# esp-streamer-schematics.net
KiCad netlist of a schematic drawn in EasyEDA Pro
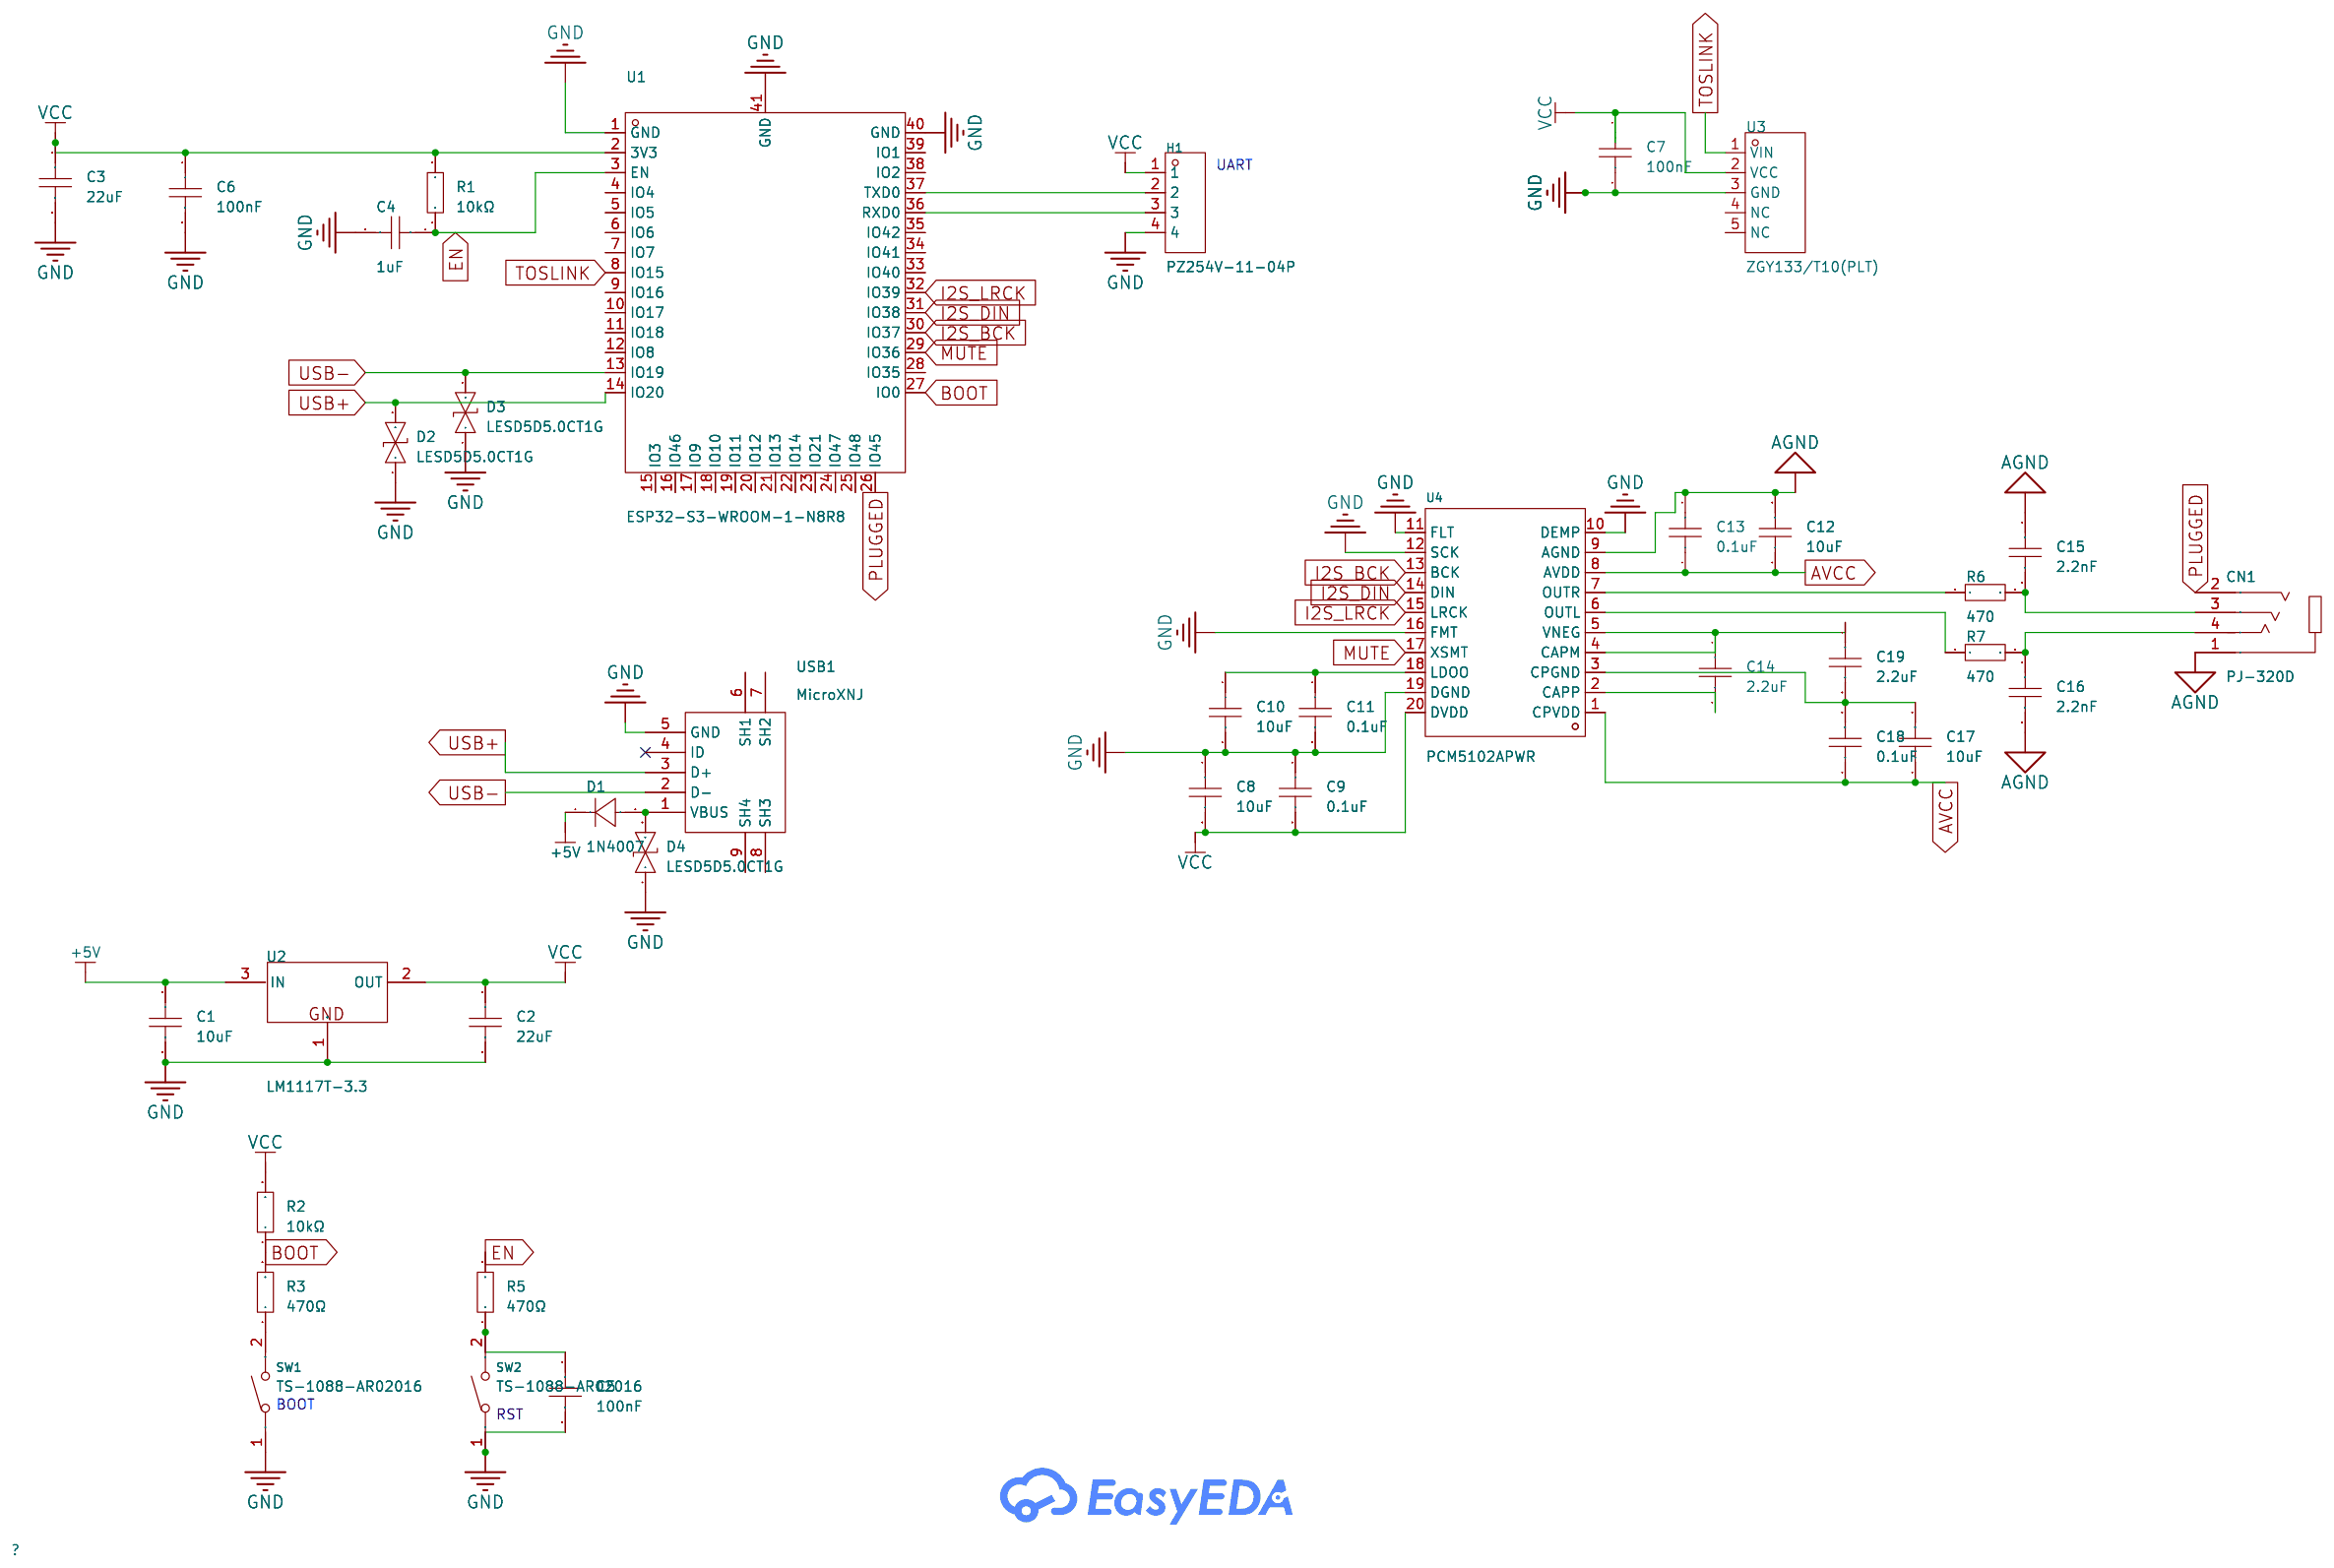
[diagram p0: schematic sheet]

(export (version "E")
  (design (tool "Eeschema 10.0.6"))
  (components
    (comp (ref "C1")
      (value "10uF")
      (footprint "easyedapro:C0603")
      (fields
        (field (name "Manufacturer Part") "CL10A106KP8NNNC")
        (field (name "Manufacturer") "SAMSUNG(三星)")
      )
      (libsource (lib "easyedapro") (part "CAP"))
    )
    (comp (ref "C2")
      (value "22uF")
      (footprint "easyedapro:C0603")
      (fields
        (field (name "Manufacturer Part") "CL10A226MQ8NRNC")
        (field (name "Manufacturer") "SAMSUNG(三星)")
      )
      (libsource (lib "easyedapro") (part "CAP"))
    )
    (comp (ref "C3")
      (value "22uF")
      (footprint "easyedapro:C0603")
      (fields
        (field (name "Manufacturer Part") "CL10A226MQ8NRNC")
        (field (name "Manufacturer") "SAMSUNG(三星)")
      )
      (libsource (lib "easyedapro") (part "CAP"))
    )
    (comp (ref "C4")
      (value "1uF")
      (footprint "easyedapro:C0603")
      (fields
        (field (name "Manufacturer Part") "CL10A105KB8NNNC")
        (field (name "Manufacturer") "SAMSUNG(三星)")
      )
      (libsource (lib "easyedapro") (part "CAP"))
    )
    (comp (ref "C5")
      (value "100nF")
      (footprint "easyedapro:C0603")
      (fields
        (field (name "Manufacturer Part") "CC0603KRX7R9BB104")
        (field (name "Manufacturer") "YAGEO(国巨)")
      )
      (libsource (lib "easyedapro") (part "CAP"))
    )
    (comp (ref "C6")
      (value "100nF")
      (footprint "easyedapro:C0603")
      (fields
        (field (name "Manufacturer Part") "CC0603KRX7R9BB104")
        (field (name "Manufacturer") "YAGEO(国巨)")
      )
      (libsource (lib "easyedapro") (part "CAP"))
    )
    (comp (ref "C7")
      (value "100nF")
      (footprint "easyedapro:C0603")
      (fields
        (field (name "Manufacturer Part") "CC0603KRX7R9BB104")
        (field (name "Manufacturer") "YAGEO(国巨)")
      )
      (libsource (lib "easyedapro") (part "CAP"))
    )
    (comp (ref "C8")
      (value "10uF")
      (footprint "easyedapro:C0603")
      (libsource (lib "easyedapro") (part "CAP"))
    )
    (comp (ref "C9")
      (value "0.1uF")
      (footprint "easyedapro:C0603")
      (libsource (lib "easyedapro") (part "CAP"))
    )
    (comp (ref "C10")
      (value "10uF")
      (footprint "easyedapro:C0603")
      (libsource (lib "easyedapro") (part "CAP"))
    )
    (comp (ref "C11")
      (value "0.1uF")
      (footprint "easyedapro:C0603")
      (libsource (lib "easyedapro") (part "CAP"))
    )
    (comp (ref "C12")
      (value "10uF")
      (footprint "easyedapro:C0603")
      (libsource (lib "easyedapro") (part "CAP"))
    )
    (comp (ref "C13")
      (value "0.1uF")
      (footprint "easyedapro:C0603")
      (libsource (lib "easyedapro") (part "CAP"))
    )
    (comp (ref "C14")
      (value "2.2uF")
      (footprint "easyedapro:C0603")
      (libsource (lib "easyedapro") (part "CAP"))
    )
    (comp (ref "C15")
      (value "2.2nF")
      (footprint "easyedapro:C0603")
      (libsource (lib "easyedapro") (part "CAP"))
    )
    (comp (ref "C16")
      (value "2.2nF")
      (footprint "easyedapro:C0603")
      (libsource (lib "easyedapro") (part "CAP"))
    )
    (comp (ref "C17")
      (value "10uF")
      (footprint "easyedapro:C0603")
      (libsource (lib "easyedapro") (part "CAP"))
    )
    (comp (ref "C18")
      (value "0.1uF")
      (footprint "easyedapro:C0603")
      (libsource (lib "easyedapro") (part "CAP"))
    )
    (comp (ref "C19")
      (value "2.2uF")
      (footprint "easyedapro:C0603")
      (libsource (lib "easyedapro") (part "CAP"))
    )
    (comp (ref "CN1")
      (value "PJ-320D")
      (footprint "easyedapro:AUDIO-SMD_PJ-320D")
      (fields (field (name "Manufacturer") "SHOU HAN(首韩)"))
      (libsource (lib "easyedapro") (part "PJ-320D"))
    )
    (comp (ref "D1")
      (value "1N4007")
      (fields (field (name "Manufacturer") "XCH(旭昌辉)"))
      (libsource (lib "easyedapro") (part "D_1N4007"))
    )
    (comp (ref "D2")
      (value "LESD5D5.0CT1G")
      (footprint "easyedapro:SOD-523_L1.2-W0.8-LS1.6-BI")
      (fields (field (name "Manufacturer") "LRC(乐山无线电)"))
      (libsource (lib "easyedapro") (part "LESD5D5.0CT1G"))
    )
    (comp (ref "D3")
      (value "LESD5D5.0CT1G")
      (footprint "easyedapro:SOD-523_L1.2-W0.8-LS1.6-BI")
      (fields (field (name "Manufacturer") "LRC(乐山无线电)"))
      (libsource (lib "easyedapro") (part "LESD5D5.0CT1G"))
    )
    (comp (ref "D4")
      (value "LESD5D5.0CT1G")
      (footprint "easyedapro:SOD-523_L1.2-W0.8-LS1.6-BI")
      (fields (field (name "Manufacturer") "LRC(乐山无线电)"))
      (libsource (lib "easyedapro") (part "LESD5D5.0CT1G"))
    )
    (comp (ref "H1")
      (value "PZ254V-11-04P")
      (footprint "easyedapro:HDR-TH_4P-P2.54-V-M")
      (fields (field (name "Manufacturer") "XFCN(兴飞)"))
      (libsource (lib "easyedapro") (part "PZ254V-11-04P_C2691448"))
    )
    (comp (ref "R1")
      (value "10kΩ")
      (footprint "easyedapro:R0603")
      (fields
        (field (name "Manufacturer Part") "0603WAF1002T5E")
        (field (name "Manufacturer") "UNI-ROYAL(厚声)")
      )
      (libsource (lib "easyedapro") (part "Res"))
    )
    (comp (ref "R2")
      (value "10kΩ")
      (footprint "easyedapro:R0603")
      (fields
        (field (name "Manufacturer Part") "0603WAF1002T5E")
        (field (name "Manufacturer") "UNI-ROYAL(厚声)")
      )
      (libsource (lib "easyedapro") (part "Res"))
    )
    (comp (ref "R3")
      (value "470Ω")
      (footprint "easyedapro:R0603")
      (fields
        (field (name "Manufacturer Part") "0603WAF4700T5E")
        (field (name "Manufacturer") "UNI-ROYAL(厚声)")
      )
      (libsource (lib "easyedapro") (part "Res"))
    )
    (comp (ref "R5")
      (value "470Ω")
      (footprint "easyedapro:R0603")
      (fields
        (field (name "Manufacturer Part") "0603WAF4700T5E")
        (field (name "Manufacturer") "UNI-ROYAL(厚声)")
      )
      (libsource (lib "easyedapro") (part "Res"))
    )
    (comp (ref "R6") (value "470") (footprint "easyedapro:R0603") (libsource (lib "easyedapro") (part "Res")))
    (comp (ref "R7") (value "470") (footprint "easyedapro:R0603") (libsource (lib "easyedapro") (part "Res")))
    (comp (ref "SW1")
      (value "TS-1088-AR02016")
      (footprint "easyedapro:SW-SMD_L3.9-W3.0-P4.45")
      (fields (field (name "Manufacturer") "XUNPU(讯普)"))
      (libsource (lib "easyedapro") (part "TS-1088-AR02016"))
    )
    (comp (ref "SW2")
      (value "TS-1088-AR02016")
      (footprint "easyedapro:SW-SMD_L3.9-W3.0-P4.45")
      (fields (field (name "Manufacturer") "XUNPU(讯普)"))
      (libsource (lib "easyedapro") (part "TS-1088-AR02016"))
    )
    (comp (ref "U1")
      (value "ESP32-S3-WROOM-1-N8R8")
      (footprint "easyedapro:WIRELM-SMD_ESP32-S3-WROOM-1")
      (fields (field (name "Manufacturer") "ESPRESSIF(乐鑫)"))
      (libsource (lib "easyedapro") (part "ESP32-S3-WROOM-1(N8R8)"))
    )
    (comp (ref "U2")
      (value "LM1117T-3.3")
      (footprint "easyedapro:TO-220-3_L10.0-W4.5-P2.54-L")
      (fields (field (name "Manufacturer") "HGSEMI(华冠)"))
      (libsource (lib "easyedapro") (part "LM1117T-3.3"))
    )
    (comp (ref "U3")
      (value "ZGY133/T10(PLT)")
      (footprint "easyedapro:COMM-TH_ZGY133-T10-PLT")
      (description "Type:Fiber optic transmitter")
      (fields (field (name "Manufacturer") "Chau Light(洲光源)"))
      (libsource (lib "easyedapro") (part "ZGY133/T10(PLT)"))
    )
    (comp (ref "U4")
      (value "PCM5102APWR")
      (footprint "easyedapro:TSSOP-20_L6.5-W4.4-P0.65-LS6.4-BL")
      (fields (field (name "Manufacturer") "TI(德州仪器)"))
      (libsource (lib "easyedapro") (part "PCM5102APWR"))
    )
    (comp (ref "USB1")
      (value "MicroXNJ")
      (footprint "easyedapro:MICRO-USB-SMD_MICROXNJ")
      (fields (field (name "Manufacturer") "SHOU HAN(首韩)"))
      (libsource (lib "easyedapro") (part "MICROXNJ"))
    )
  )
  (nets
    (net (code "1") (name "+5V") (class "Default")
      (node (ref "C1") (pin "1") (pinfunction "1_1") (pintype "input"))
      (node (ref "D1") (pin "1") (pinfunction "K_1") (pintype "input"))
      (node (ref "U2") (pin "3") (pinfunction "IN_3") (pintype "unspecified"))
    )
    (net (code "2") (name "AGND") (class "Default")
      (node (ref "C12") (pin "2") (pinfunction "2_2") (pintype "input"))
      (node (ref "C13") (pin "2") (pinfunction "2_2") (pintype "input"))
      (node (ref "C15") (pin "1") (pinfunction "1_1") (pintype "input"))
      (node (ref "C16") (pin "2") (pinfunction "2_2") (pintype "input"))
      (node (ref "CN1") (pin "1") (pinfunction "1_1") (pintype "unspecified"))
      (node (ref "U4") (pin "9") (pinfunction "AGND_9") (pintype "input"))
    )
    (net (code "3") (name "AVCC") (class "Default")
      (node (ref "C12") (pin "1") (pinfunction "1_1") (pintype "input"))
      (node (ref "C13") (pin "1") (pinfunction "1_1") (pintype "input"))
      (node (ref "C17") (pin "1") (pinfunction "1_1") (pintype "input"))
      (node (ref "C18") (pin "1") (pinfunction "1_1") (pintype "input"))
      (node (ref "U4") (pin "1") (pinfunction "CPVDD_1") (pintype "input"))
      (node (ref "U4") (pin "8") (pinfunction "AVDD_8") (pintype "input"))
    )
    (net (code "4") (name "BOOT") (class "Default")
      (node (ref "R2") (pin "1") (pinfunction "1_1") (pintype "input"))
      (node (ref "R3") (pin "2") (pinfunction "2_2") (pintype "input"))
      (node (ref "U1") (pin "27") (pinfunction "IO0_27") (pintype "unspecified"))
    )
    (net (code "5") (name "EN") (class "Default")
      (node (ref "C4") (pin "1") (pinfunction "1_1") (pintype "input"))
      (node (ref "R1") (pin "1") (pinfunction "1_1") (pintype "input"))
      (node (ref "R5") (pin "2") (pinfunction "2_2") (pintype "input"))
      (node (ref "U1") (pin "3") (pinfunction "EN_3") (pintype "unspecified"))
    )
    (net (code "6") (name "GND") (class "Default")
      (node (ref "C1") (pin "2") (pinfunction "2_2") (pintype "input"))
      (node (ref "C10") (pin "2") (pinfunction "2_2") (pintype "input"))
      (node (ref "C11") (pin "2") (pinfunction "2_2") (pintype "input"))
      (node (ref "C2") (pin "2") (pinfunction "2_2") (pintype "input"))
      (node (ref "C3") (pin "2") (pinfunction "2_2") (pintype "input"))
      (node (ref "C4") (pin "2") (pinfunction "2_2") (pintype "input"))
      (node (ref "C5") (pin "2") (pinfunction "2_2") (pintype "input"))
      (node (ref "C6") (pin "2") (pinfunction "2_2") (pintype "input"))
      (node (ref "C7") (pin "2") (pinfunction "2_2") (pintype "input"))
      (node (ref "C8") (pin "1") (pinfunction "1_1") (pintype "input"))
      (node (ref "C9") (pin "1") (pinfunction "1_1") (pintype "input"))
      (node (ref "D2") (pin "1") (pinfunction "1_1") (pintype "unspecified"))
      (node (ref "D3") (pin "1") (pinfunction "1_1") (pintype "unspecified"))
      (node (ref "D4") (pin "1") (pinfunction "1_1") (pintype "unspecified"))
      (node (ref "H1") (pin "4") (pinfunction "4_4") (pintype "input"))
      (node (ref "SW1") (pin "1") (pinfunction "1_1") (pintype "input"))
      (node (ref "SW2") (pin "1") (pinfunction "1_1") (pintype "input"))
      (node (ref "U1") (pin "1") (pinfunction "GND_1") (pintype "unspecified"))
      (node (ref "U1") (pin "40") (pinfunction "GND_40") (pintype "unspecified"))
      (node (ref "U1") (pin "41") (pinfunction "GND_41") (pintype "unspecified"))
      (node (ref "U2") (pin "1") (pinfunction "GND_1") (pintype "unspecified"))
      (node (ref "U3") (pin "3") (pinfunction "GND_3") (pintype "unspecified"))
      (node (ref "U4") (pin "10") (pinfunction "DEMP_10") (pintype "input"))
      (node (ref "U4") (pin "11") (pinfunction "FLT_11") (pintype "input"))
      (node (ref "U4") (pin "12") (pinfunction "SCK_12") (pintype "input"))
      (node (ref "U4") (pin "16") (pinfunction "FMT_16") (pintype "input"))
      (node (ref "U4") (pin "19") (pinfunction "DGND_19") (pintype "input"))
      (node (ref "USB1") (pin "5") (pinfunction "GND_5") (pintype "unspecified"))
    )
    (net (code "7") (name "I2S_BCK") (class "Default")
      (node (ref "U1") (pin "30") (pinfunction "IO37_30") (pintype "unspecified"))
      (node (ref "U4") (pin "13") (pinfunction "BCK_13") (pintype "input"))
    )
    (net (code "8") (name "I2S_DIN") (class "Default")
      (node (ref "U1") (pin "31") (pinfunction "IO38_31") (pintype "unspecified"))
      (node (ref "U4") (pin "14") (pinfunction "DIN_14") (pintype "input"))
    )
    (net (code "9") (name "I2S_LRCK") (class "Default")
      (node (ref "U1") (pin "32") (pinfunction "IO39_32") (pintype "unspecified"))
      (node (ref "U4") (pin "15") (pinfunction "LRCK_15") (pintype "input"))
    )
    (net (code "10") (name "MUTE") (class "Default")
      (node (ref "U1") (pin "29") (pinfunction "IO36_29") (pintype "unspecified"))
      (node (ref "U4") (pin "17") (pinfunction "XSMT_17") (pintype "input"))
    )
    (net (code "11") (name "Net-(C5-Pad1)") (class "Default")
      (node (ref "C5") (pin "1") (pinfunction "1_1") (pintype "input"))
      (node (ref "R5") (pin "1") (pinfunction "1_1") (pintype "input"))
      (node (ref "SW2") (pin "2") (pinfunction "2_2") (pintype "input"))
    )
    (net (code "12") (name "Net-(C15-Pad2)") (class "Default")
      (node (ref "C15") (pin "2") (pinfunction "2_2") (pintype "input"))
      (node (ref "CN1") (pin "3") (pinfunction "3_3") (pintype "unspecified"))
      (node (ref "R6") (pin "2") (pinfunction "2_2") (pintype "input"))
    )
    (net (code "13") (name "Net-(C16-Pad1)") (class "Default")
      (node (ref "C16") (pin "1") (pinfunction "1_1") (pintype "input"))
      (node (ref "CN1") (pin "4") (pinfunction "4_4") (pintype "unspecified"))
      (node (ref "R7") (pin "2") (pinfunction "2_2") (pintype "input"))
    )
    (net (code "14") (name "Net-(D1-A)") (class "Default")
      (node (ref "D1") (pin "2") (pinfunction "A_2") (pintype "input"))
      (node (ref "D4") (pin "2") (pinfunction "2_2") (pintype "unspecified"))
      (node (ref "USB1") (pin "1") (pinfunction "VBUS_1") (pintype "unspecified"))
    )
    (net (code "15") (name "Net-(R3-Pad1)") (class "Default")
      (node (ref "R3") (pin "1") (pinfunction "1_1") (pintype "input"))
      (node (ref "SW1") (pin "2") (pinfunction "2_2") (pintype "input"))
    )
    (net (code "16") (name "Net-(U1-RXD0)") (class "Default")
      (node (ref "H1") (pin "3") (pinfunction "3_3") (pintype "input"))
      (node (ref "U1") (pin "36") (pinfunction "RXD0_36") (pintype "unspecified"))
    )
    (net (code "17") (name "Net-(U1-TXD0)") (class "Default")
      (node (ref "H1") (pin "2") (pinfunction "2_2") (pintype "input"))
      (node (ref "U1") (pin "37") (pinfunction "TXD0_37") (pintype "unspecified"))
    )
    (net (code "18") (name "Net-(U4-CAPM)") (class "Default")
      (node (ref "C14") (pin "1") (pinfunction "1_1") (pintype "input"))
      (node (ref "C19") (pin "1") (pinfunction "1_1") (pintype "input"))
      (node (ref "U4") (pin "4") (pinfunction "CAPM_4") (pintype "input"))
      (node (ref "U4") (pin "5") (pinfunction "VNEG_5") (pintype "input"))
    )
    (net (code "19") (name "Net-(U4-CAPP)") (class "Default")
      (node (ref "C14") (pin "2") (pinfunction "2_2") (pintype "input"))
      (node (ref "U4") (pin "2") (pinfunction "CAPP_2") (pintype "input"))
    )
    (net (code "20") (name "Net-(U4-CPGND)") (class "Default")
      (node (ref "C17") (pin "2") (pinfunction "2_2") (pintype "input"))
      (node (ref "C18") (pin "2") (pinfunction "2_2") (pintype "input"))
      (node (ref "C19") (pin "2") (pinfunction "2_2") (pintype "input"))
      (node (ref "U4") (pin "3") (pinfunction "CPGND_3") (pintype "input"))
    )
    (net (code "21") (name "Net-(U4-LDOO)") (class "Default")
      (node (ref "C10") (pin "1") (pinfunction "1_1") (pintype "input"))
      (node (ref "C11") (pin "1") (pinfunction "1_1") (pintype "input"))
      (node (ref "U4") (pin "18") (pinfunction "LDOO_18") (pintype "input"))
    )
    (net (code "22") (name "Net-(U4-OUTL)") (class "Default")
      (node (ref "R7") (pin "1") (pinfunction "1_1") (pintype "input"))
      (node (ref "U4") (pin "6") (pinfunction "OUTL_6") (pintype "input"))
    )
    (net (code "23") (name "Net-(U4-OUTR)") (class "Default")
      (node (ref "R6") (pin "1") (pinfunction "1_1") (pintype "input"))
      (node (ref "U4") (pin "7") (pinfunction "OUTR_7") (pintype "input"))
    )
    (net (code "24") (name "PLUGGED") (class "Default")
      (node (ref "CN1") (pin "2") (pinfunction "2_2") (pintype "unspecified"))
      (node (ref "U1") (pin "26") (pinfunction "IO45_26") (pintype "unspecified"))
    )
    (net (code "25") (name "TOSLINK") (class "Default")
      (node (ref "U1") (pin "8") (pinfunction "IO15_8") (pintype "unspecified"))
      (node (ref "U3") (pin "1") (pinfunction "VIN_1") (pintype "unspecified"))
    )
    (net (code "26") (name "USB+") (class "Default")
      (node (ref "D2") (pin "2") (pinfunction "2_2") (pintype "unspecified"))
      (node (ref "U1") (pin "14") (pinfunction "IO20_14") (pintype "unspecified"))
      (node (ref "USB1") (pin "3") (pinfunction "D+_3") (pintype "unspecified"))
    )
    (net (code "27") (name "USB-") (class "Default")
      (node (ref "D3") (pin "2") (pinfunction "2_2") (pintype "unspecified"))
      (node (ref "U1") (pin "13") (pinfunction "IO19_13") (pintype "unspecified"))
      (node (ref "USB1") (pin "2") (pinfunction "D-_2") (pintype "unspecified"))
    )
    (net (code "28") (name "VCC") (class "Default")
      (node (ref "C2") (pin "1") (pinfunction "1_1") (pintype "input"))
      (node (ref "C3") (pin "1") (pinfunction "1_1") (pintype "input"))
      (node (ref "C6") (pin "1") (pinfunction "1_1") (pintype "input"))
      (node (ref "C7") (pin "1") (pinfunction "1_1") (pintype "input"))
      (node (ref "C8") (pin "2") (pinfunction "2_2") (pintype "input"))
      (node (ref "C9") (pin "2") (pinfunction "2_2") (pintype "input"))
      (node (ref "H1") (pin "1") (pinfunction "1_1") (pintype "input"))
      (node (ref "R1") (pin "2") (pinfunction "2_2") (pintype "input"))
      (node (ref "R2") (pin "2") (pinfunction "2_2") (pintype "input"))
      (node (ref "U1") (pin "2") (pinfunction "3V3_2") (pintype "unspecified"))
      (node (ref "U2") (pin "2") (pinfunction "OUT_2") (pintype "unspecified"))
      (node (ref "U3") (pin "2") (pinfunction "VCC_2") (pintype "unspecified"))
      (node (ref "U4") (pin "20") (pinfunction "DVDD_20") (pintype "input"))
    )
    (net (code "29") (name "unconnected-(U1-IO1-Pad39)") (class "Default")
      (node (ref "U1") (pin "39") (pinfunction "IO1_39") (pintype "unspecified"))
    )
    (net (code "30") (name "unconnected-(U1-IO2-Pad38)") (class "Default")
      (node (ref "U1") (pin "38") (pinfunction "IO2_38") (pintype "unspecified"))
    )
    (net (code "31") (name "unconnected-(U1-IO3-Pad15)") (class "Default")
      (node (ref "U1") (pin "15") (pinfunction "IO3_15") (pintype "unspecified"))
    )
    (net (code "32") (name "unconnected-(U1-IO4-Pad4)") (class "Default")
      (node (ref "U1") (pin "4") (pinfunction "IO4_4") (pintype "unspecified"))
    )
    (net (code "33") (name "unconnected-(U1-IO5-Pad5)") (class "Default")
      (node (ref "U1") (pin "5") (pinfunction "IO5_5") (pintype "unspecified"))
    )
    (net (code "34") (name "unconnected-(U1-IO6-Pad6)") (class "Default")
      (node (ref "U1") (pin "6") (pinfunction "IO6_6") (pintype "unspecified"))
    )
    (net (code "35") (name "unconnected-(U1-IO7-Pad7)") (class "Default")
      (node (ref "U1") (pin "7") (pinfunction "IO7_7") (pintype "unspecified"))
    )
    (net (code "36") (name "unconnected-(U1-IO8-Pad12)") (class "Default")
      (node (ref "U1") (pin "12") (pinfunction "IO8_12") (pintype "unspecified"))
    )
    (net (code "37") (name "unconnected-(U1-IO9-Pad17)") (class "Default")
      (node (ref "U1") (pin "17") (pinfunction "IO9_17") (pintype "unspecified"))
    )
    (net (code "38") (name "unconnected-(U1-IO10-Pad18)") (class "Default")
      (node (ref "U1") (pin "18") (pinfunction "IO10_18") (pintype "unspecified"))
    )
    (net (code "39") (name "unconnected-(U1-IO11-Pad19)") (class "Default")
      (node (ref "U1") (pin "19") (pinfunction "IO11_19") (pintype "unspecified"))
    )
    (net (code "40") (name "unconnected-(U1-IO12-Pad20)") (class "Default")
      (node (ref "U1") (pin "20") (pinfunction "IO12_20") (pintype "unspecified"))
    )
    (net (code "41") (name "unconnected-(U1-IO13-Pad21)") (class "Default")
      (node (ref "U1") (pin "21") (pinfunction "IO13_21") (pintype "unspecified"))
    )
    (net (code "42") (name "unconnected-(U1-IO14-Pad22)") (class "Default")
      (node (ref "U1") (pin "22") (pinfunction "IO14_22") (pintype "unspecified"))
    )
    (net (code "43") (name "unconnected-(U1-IO16-Pad9)") (class "Default")
      (node (ref "U1") (pin "9") (pinfunction "IO16_9") (pintype "unspecified"))
    )
    (net (code "44") (name "unconnected-(U1-IO17-Pad10)") (class "Default")
      (node (ref "U1") (pin "10") (pinfunction "IO17_10") (pintype "unspecified"))
    )
    (net (code "45") (name "unconnected-(U1-IO18-Pad11)") (class "Default")
      (node (ref "U1") (pin "11") (pinfunction "IO18_11") (pintype "unspecified"))
    )
    (net (code "46") (name "unconnected-(U1-IO21-Pad23)") (class "Default")
      (node (ref "U1") (pin "23") (pinfunction "IO21_23") (pintype "unspecified"))
    )
    (net (code "47") (name "unconnected-(U1-IO35-Pad28)") (class "Default")
      (node (ref "U1") (pin "28") (pinfunction "IO35_28") (pintype "unspecified"))
    )
    (net (code "48") (name "unconnected-(U1-IO40-Pad33)") (class "Default")
      (node (ref "U1") (pin "33") (pinfunction "IO40_33") (pintype "unspecified"))
    )
    (net (code "49") (name "unconnected-(U1-IO41-Pad34)") (class "Default")
      (node (ref "U1") (pin "34") (pinfunction "IO41_34") (pintype "unspecified"))
    )
    (net (code "50") (name "unconnected-(U1-IO42-Pad35)") (class "Default")
      (node (ref "U1") (pin "35") (pinfunction "IO42_35") (pintype "unspecified"))
    )
    (net (code "51") (name "unconnected-(U1-IO46-Pad16)") (class "Default")
      (node (ref "U1") (pin "16") (pinfunction "IO46_16") (pintype "unspecified"))
    )
    (net (code "52") (name "unconnected-(U1-IO47-Pad24)") (class "Default")
      (node (ref "U1") (pin "24") (pinfunction "IO47_24") (pintype "unspecified"))
    )
    (net (code "53") (name "unconnected-(U1-IO48-Pad25)") (class "Default")
      (node (ref "U1") (pin "25") (pinfunction "IO48_25") (pintype "unspecified"))
    )
    (net (code "54") (name "unconnected-(U3-NC-Pad4)") (class "Default")
      (node (ref "U3") (pin "4") (pinfunction "NC_4") (pintype "unspecified"))
    )
    (net (code "55") (name "unconnected-(U3-NC-Pad5)") (class "Default")
      (node (ref "U3") (pin "5") (pinfunction "NC_5") (pintype "unspecified"))
    )
    (net (code "56") (name "unconnected-(USB1-ID-Pad4)") (class "Default")
      (node (ref "USB1") (pin "4") (pinfunction "ID_4") (pintype "unspecified+no_connect"))
    )
    (net (code "57") (name "unconnected-(USB1-SH1-Pad6)") (class "Default")
      (node (ref "USB1") (pin "6") (pinfunction "SH1_6") (pintype "unspecified"))
    )
    (net (code "58") (name "unconnected-(USB1-SH2-Pad7)") (class "Default")
      (node (ref "USB1") (pin "7") (pinfunction "SH2_7") (pintype "unspecified"))
    )
    (net (code "59") (name "unconnected-(USB1-SH3-Pad8)") (class "Default")
      (node (ref "USB1") (pin "8") (pinfunction "SH3_8") (pintype "unspecified"))
    )
    (net (code "60") (name "unconnected-(USB1-SH4-Pad9)") (class "Default")
      (node (ref "USB1") (pin "9") (pinfunction "SH4_9") (pintype "unspecified"))
    )
  )
)
